# ir_remote_v3.net
KiCad netlist of a schematic drawn in EAGLE
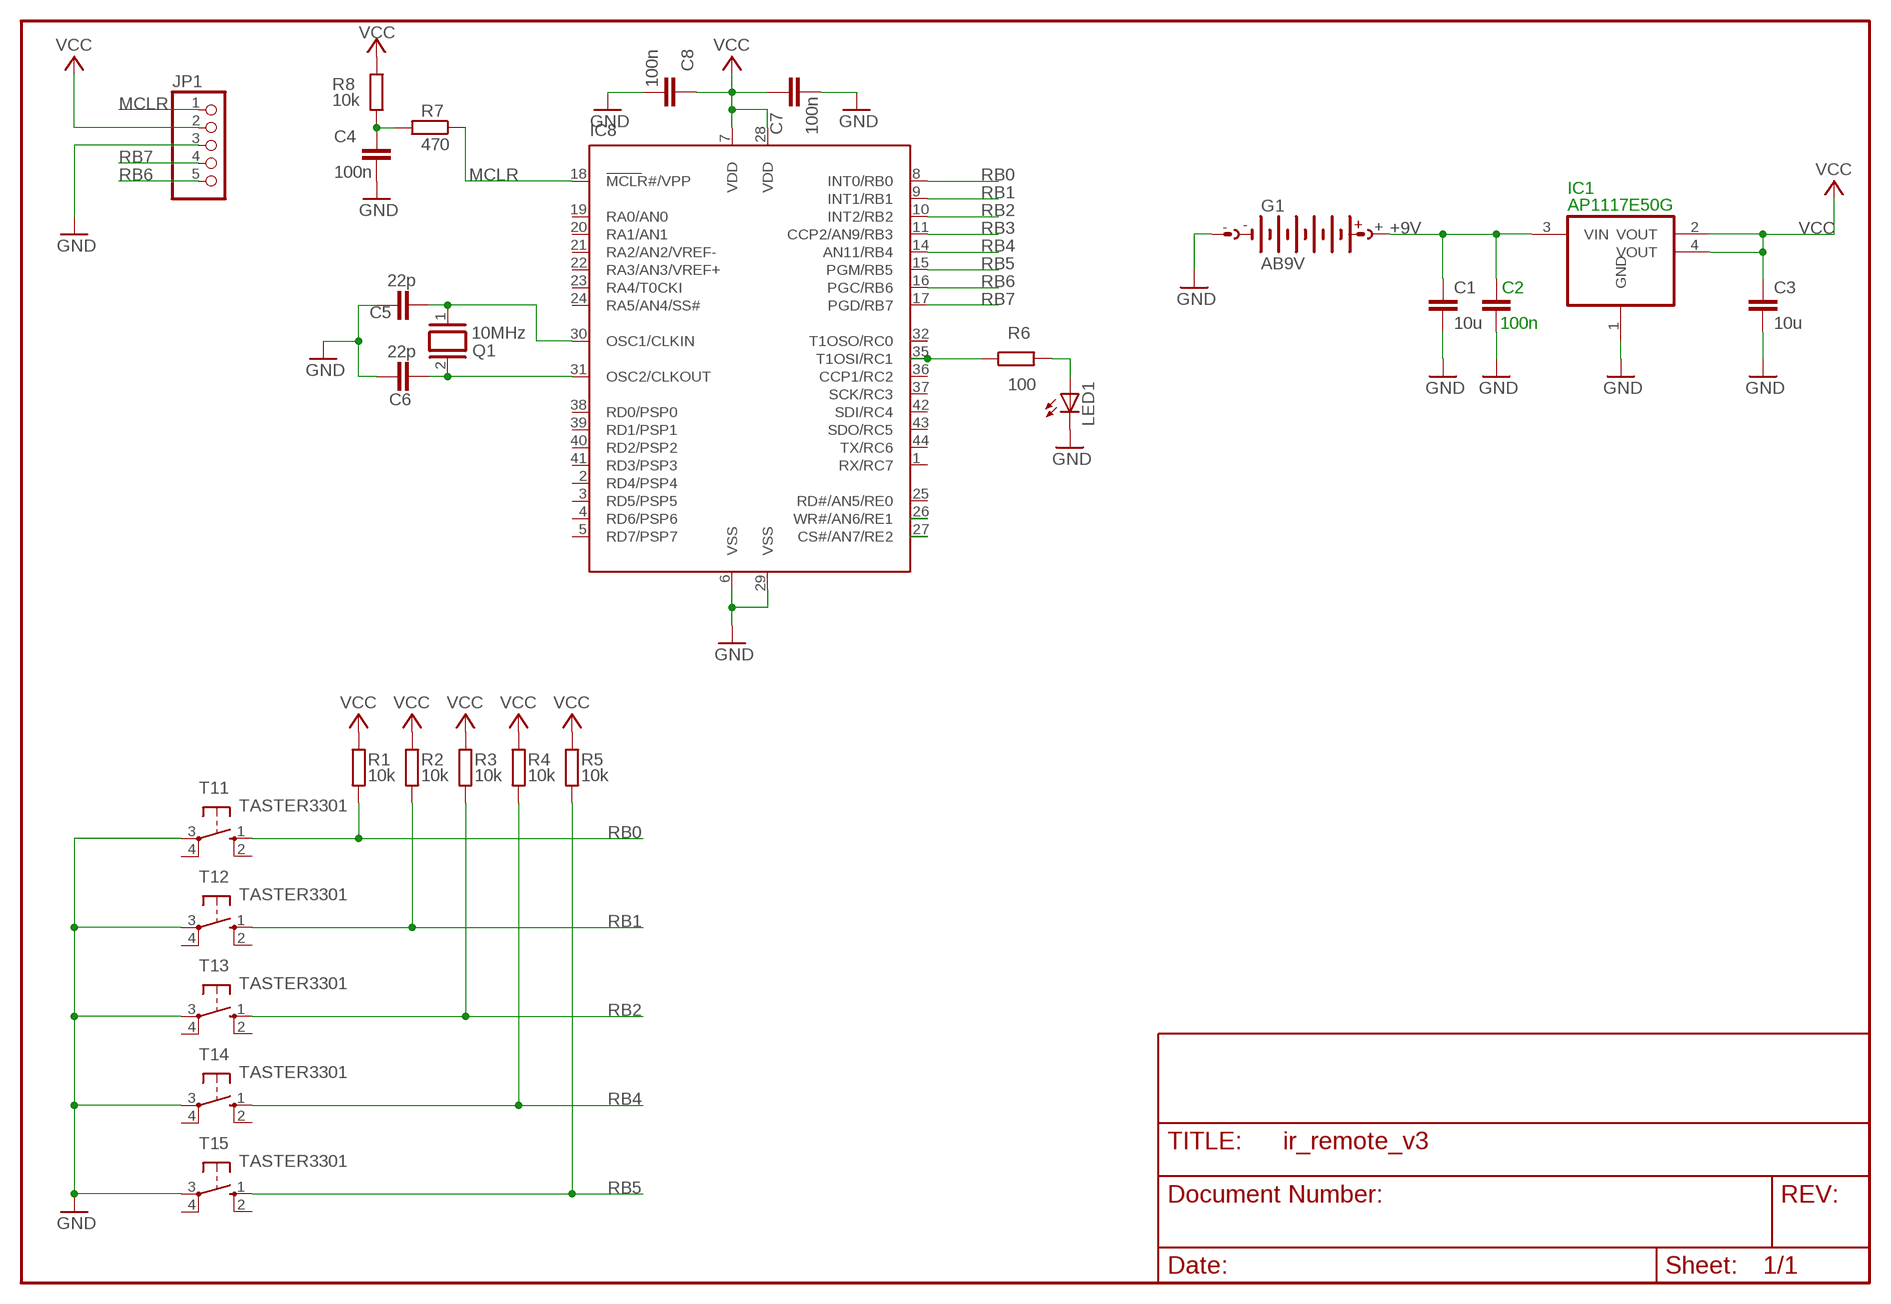
[diagram p0: schematic, sheet 1]

(export (version "E")
  (design (tool "Eeschema 10.0.6"))
  (components
    (comp (ref "C1")
      (value "10u")
      (footprint "eagle-import:C0805")
      (libsource (lib "eagle-import") (part "C-EUC0805"))
    )
    (comp (ref "C2")
      (value "100n")
      (footprint "eagle-import:C0805")
      (libsource (lib "eagle-import") (part "rcl_416_C-EUC0805"))
    )
    (comp (ref "C3")
      (value "10u")
      (footprint "eagle-import:C0805")
      (libsource (lib "eagle-import") (part "C-EUC0805"))
    )
    (comp (ref "C4")
      (value "100n")
      (footprint "eagle-import:C0805")
      (libsource (lib "eagle-import") (part "C-EUC0805"))
    )
    (comp (ref "C5")
      (value "22p")
      (footprint "eagle-import:C0603_WE")
      (libsource (lib "eagle-import") (part "C-EUC0603_WE"))
    )
    (comp (ref "C6")
      (value "22p")
      (footprint "eagle-import:C0603_WE")
      (libsource (lib "eagle-import") (part "C-EUC0603_WE"))
    )
    (comp (ref "C7")
      (value "100n")
      (footprint "eagle-import:C0805")
      (libsource (lib "eagle-import") (part "C-EUC0805"))
    )
    (comp (ref "C8")
      (value "100n")
      (footprint "eagle-import:C0805")
      (libsource (lib "eagle-import") (part "C-EUC0805"))
    )
    (comp (ref "G1")
      (value "AB9V")
      (footprint "eagle-import:AB9V")
      (libsource (lib "eagle-import") (part "AB9V"))
    )
    (comp (ref "IC1")
      (value "AP1117E50G")
      (footprint "eagle-import:SOT223")
      (libsource (lib "eagle-import") (part "REG1117-2OUT"))
    )
    (comp (ref "IC8")
      (value "PIC18F4520")
      (footprint "eagle-import:TQFP44")
      (libsource (lib "eagle-import") (part "PIC18F4520"))
    )
    (comp (ref "JP1")
      (value "PINHD-1X5")
      (footprint "eagle-import:1X05")
      (libsource (lib "eagle-import") (part "PINHD-1X5"))
    )
    (comp (ref "LED1")
      (value "LED5MM")
      (footprint "eagle-import:LED5MM")
      (libsource (lib "eagle-import") (part "LED5MM"))
    )
    (comp (ref "Q1")
      (value "10MHz")
      (footprint "eagle-import:QUARZ_HC5032_2")
      (libsource (lib "eagle-import") (part "XTAL_HC5032"))
    )
    (comp (ref "R1")
      (value "10k")
      (footprint "eagle-import:M0805")
      (libsource (lib "eagle-import") (part "R-EU_M0805"))
    )
    (comp (ref "R2")
      (value "10k")
      (footprint "eagle-import:M0805")
      (libsource (lib "eagle-import") (part "R-EU_M0805"))
    )
    (comp (ref "R3")
      (value "10k")
      (footprint "eagle-import:M0805")
      (libsource (lib "eagle-import") (part "R-EU_M0805"))
    )
    (comp (ref "R4")
      (value "10k")
      (footprint "eagle-import:M0805")
      (libsource (lib "eagle-import") (part "R-EU_M0805"))
    )
    (comp (ref "R5")
      (value "10k")
      (footprint "eagle-import:M0805")
      (libsource (lib "eagle-import") (part "R-EU_M0805"))
    )
    (comp (ref "R6")
      (value "100")
      (footprint "eagle-import:M0805")
      (libsource (lib "eagle-import") (part "R-EU_M0805"))
    )
    (comp (ref "R7")
      (value "470")
      (footprint "eagle-import:M0805")
      (libsource (lib "eagle-import") (part "R-EU_M0805"))
    )
    (comp (ref "R8")
      (value "10k")
      (footprint "eagle-import:M0805")
      (libsource (lib "eagle-import") (part "R-EU_M0805"))
    )
    (comp (ref "T11")
      (value "TASTER3301")
      (footprint "eagle-import:TASTER3301")
      (libsource (lib "eagle-import") (part "TASTER3301"))
    )
    (comp (ref "T12")
      (value "TASTER3301")
      (footprint "eagle-import:TASTER3301")
      (libsource (lib "eagle-import") (part "TASTER3301"))
    )
    (comp (ref "T13")
      (value "TASTER3301")
      (footprint "eagle-import:TASTER3301")
      (libsource (lib "eagle-import") (part "TASTER3301"))
    )
    (comp (ref "T14")
      (value "TASTER3301")
      (footprint "eagle-import:TASTER3301")
      (libsource (lib "eagle-import") (part "TASTER3301"))
    )
    (comp (ref "T15")
      (value "TASTER3301")
      (footprint "eagle-import:TASTER3301")
      (libsource (lib "eagle-import") (part "TASTER3301"))
    )
  )
  (nets
    (net (code "1") (name "/+9V") (class "Default")
      (node (ref "C1") (pin "1") (pinfunction "1_1") (pintype "passive"))
      (node (ref "C2") (pin "1") (pinfunction "1_1") (pintype "passive"))
      (node (ref "G1") (pin "+") (pinfunction "+_+") (pintype "passive"))
      (node (ref "IC1") (pin "3") (pinfunction "VIN_3") (pintype "input"))
    )
    (net (code "2") (name "/MCLR") (class "Default")
      (node (ref "IC8") (pin "18") (pinfunction "MCLR#/VPP_18") (pintype "input"))
      (node (ref "JP1") (pin "1") (pinfunction "1_1") (pintype "passive"))
      (node (ref "R7") (pin "1") (pinfunction "1_1") (pintype "passive"))
    )
    (net (code "3") (name "/RB0") (class "Default")
      (node (ref "IC8") (pin "8") (pinfunction "INT0/RB0_8") (pintype "bidirectional"))
      (node (ref "R1") (pin "2") (pinfunction "2_2") (pintype "passive"))
      (node (ref "T11") (pin "1") (pinfunction "S_1") (pintype "passive"))
    )
    (net (code "4") (name "/RB1") (class "Default")
      (node (ref "IC8") (pin "9") (pinfunction "INT1/RB1_9") (pintype "bidirectional"))
      (node (ref "R2") (pin "2") (pinfunction "2_2") (pintype "passive"))
      (node (ref "T12") (pin "1") (pinfunction "S_1") (pintype "passive"))
    )
    (net (code "5") (name "/RB2") (class "Default")
      (node (ref "IC8") (pin "10") (pinfunction "INT2/RB2_10") (pintype "bidirectional"))
      (node (ref "IC8") (pin "32") (pinfunction "T1OSO/RC0_32") (pintype "bidirectional"))
      (node (ref "R3") (pin "2") (pinfunction "2_2") (pintype "passive"))
      (node (ref "T13") (pin "1") (pinfunction "S_1") (pintype "passive"))
    )
    (net (code "6") (name "/RB3") (class "Default")
      (node (ref "IC8") (pin "11") (pinfunction "CCP2/AN9/RB3_11") (pintype "bidirectional"))
    )
    (net (code "7") (name "/RB4") (class "Default")
      (node (ref "IC8") (pin "14") (pinfunction "AN11/RB4_14") (pintype "bidirectional"))
      (node (ref "R4") (pin "2") (pinfunction "2_2") (pintype "passive"))
      (node (ref "T14") (pin "1") (pinfunction "S_1") (pintype "passive"))
    )
    (net (code "8") (name "/RB5") (class "Default")
      (node (ref "IC8") (pin "15") (pinfunction "PGM/RB5_15") (pintype "bidirectional"))
      (node (ref "R5") (pin "2") (pinfunction "2_2") (pintype "passive"))
      (node (ref "T15") (pin "1") (pinfunction "S_1") (pintype "passive"))
    )
    (net (code "9") (name "/RB6") (class "Default")
      (node (ref "IC8") (pin "16") (pinfunction "PGC/RB6_16") (pintype "bidirectional"))
      (node (ref "JP1") (pin "5") (pinfunction "5_5") (pintype "passive"))
    )
    (net (code "10") (name "/RB7") (class "Default")
      (node (ref "IC8") (pin "17") (pinfunction "PGD/RB7_17") (pintype "bidirectional"))
      (node (ref "JP1") (pin "4") (pinfunction "4_4") (pintype "passive"))
    )
    (net (code "11") (name "GND") (class "Default")
      (node (ref "C1") (pin "2") (pinfunction "2_2") (pintype "passive"))
      (node (ref "C2") (pin "2") (pinfunction "2_2") (pintype "passive"))
      (node (ref "C3") (pin "2") (pinfunction "2_2") (pintype "passive"))
      (node (ref "C4") (pin "2") (pinfunction "2_2") (pintype "passive"))
      (node (ref "C5") (pin "1") (pinfunction "1_1") (pintype "passive"))
      (node (ref "C6") (pin "1") (pinfunction "1_1") (pintype "passive"))
      (node (ref "C7") (pin "2") (pinfunction "2_2") (pintype "passive"))
      (node (ref "C8") (pin "2") (pinfunction "2_2") (pintype "passive"))
      (node (ref "G1") (pin "-") (pinfunction "-_-") (pintype "passive"))
      (node (ref "IC1") (pin "1") (pinfunction "GND_1") (pintype "power_in"))
      (node (ref "IC8") (pin "29") (pinfunction "VSS_29") (pintype "bidirectional"))
      (node (ref "IC8") (pin "6") (pinfunction "VSS_6") (pintype "bidirectional"))
      (node (ref "JP1") (pin "3") (pinfunction "3_3") (pintype "passive"))
      (node (ref "LED1") (pin "K") (pinfunction "C_K") (pintype "passive"))
      (node (ref "T11") (pin "3") (pinfunction "P_3") (pintype "passive"))
      (node (ref "T12") (pin "3") (pinfunction "P_3") (pintype "passive"))
      (node (ref "T13") (pin "3") (pinfunction "P_3") (pintype "passive"))
      (node (ref "T14") (pin "3") (pinfunction "P_3") (pintype "passive"))
      (node (ref "T15") (pin "3") (pinfunction "P_3") (pintype "passive"))
    )
    (net (code "12") (name "Net-(C4-Pad1)") (class "Default")
      (node (ref "C4") (pin "1") (pinfunction "1_1") (pintype "passive"))
      (node (ref "R7") (pin "2") (pinfunction "2_2") (pintype "passive"))
      (node (ref "R8") (pin "2") (pinfunction "2_2") (pintype "passive"))
    )
    (net (code "13") (name "Net-(IC8-OSC1{slash}CLKIN)") (class "Default")
      (node (ref "C5") (pin "2") (pinfunction "2_2") (pintype "passive"))
      (node (ref "IC8") (pin "30") (pinfunction "OSC1/CLKIN_30") (pintype "input"))
      (node (ref "Q1") (pin "1") (pinfunction "1_1") (pintype "passive"))
    )
    (net (code "14") (name "Net-(IC8-OSC2{slash}CLKOUT)") (class "Default")
      (node (ref "C6") (pin "2") (pinfunction "2_2") (pintype "passive"))
      (node (ref "IC8") (pin "31") (pinfunction "OSC2/CLKOUT_31") (pintype "output"))
      (node (ref "Q1") (pin "2") (pinfunction "2_2") (pintype "passive"))
    )
    (net (code "15") (name "Net-(IC8-T1OSI{slash}RC1)") (class "Default")
      (node (ref "IC8") (pin "35") (pinfunction "T1OSI/RC1_35") (pintype "bidirectional"))
      (node (ref "R6") (pin "1") (pinfunction "1_1") (pintype "passive"))
    )
    (net (code "16") (name "Net-(LED1-PadA)") (class "Default")
      (node (ref "LED1") (pin "A") (pinfunction "A_A") (pintype "passive"))
      (node (ref "R6") (pin "2") (pinfunction "2_2") (pintype "passive"))
    )
    (net (code "17") (name "VCC") (class "Default")
      (node (ref "C3") (pin "1") (pinfunction "1_1") (pintype "passive"))
      (node (ref "C7") (pin "1") (pinfunction "1_1") (pintype "passive"))
      (node (ref "C8") (pin "1") (pinfunction "1_1") (pintype "passive"))
      (node (ref "IC1") (pin "2") (pinfunction "VOUT_2") (pintype "output"))
      (node (ref "IC1") (pin "4") (pinfunction "VOUT_4") (pintype "bidirectional"))
      (node (ref "IC8") (pin "28") (pinfunction "VDD_28") (pintype "bidirectional"))
      (node (ref "IC8") (pin "7") (pinfunction "VDD_7") (pintype "bidirectional"))
      (node (ref "JP1") (pin "2") (pinfunction "2_2") (pintype "passive"))
      (node (ref "R1") (pin "1") (pinfunction "1_1") (pintype "passive"))
      (node (ref "R2") (pin "1") (pinfunction "1_1") (pintype "passive"))
      (node (ref "R3") (pin "1") (pinfunction "1_1") (pintype "passive"))
      (node (ref "R4") (pin "1") (pinfunction "1_1") (pintype "passive"))
      (node (ref "R5") (pin "1") (pinfunction "1_1") (pintype "passive"))
      (node (ref "R8") (pin "1") (pinfunction "1_1") (pintype "passive"))
    )
    (net (code "18") (name "unconnected-(IC8-CCP1{slash}RC2-Pad36)") (class "Default")
      (node (ref "IC8") (pin "36") (pinfunction "CCP1/RC2_36") (pintype "bidirectional"))
    )
    (net (code "19") (name "unconnected-(IC8-CS#{slash}AN7{slash}RE2-Pad27)") (class "Default")
      (node (ref "IC8") (pin "27") (pinfunction "CS#/AN7/RE2_27") (pintype "bidirectional"))
    )
    (net (code "20") (name "unconnected-(IC8-RA0{slash}AN0-Pad19)") (class "Default")
      (node (ref "IC8") (pin "19") (pinfunction "RA0/AN0_19") (pintype "bidirectional"))
    )
    (net (code "21") (name "unconnected-(IC8-RA1{slash}AN1-Pad20)") (class "Default")
      (node (ref "IC8") (pin "20") (pinfunction "RA1/AN1_20") (pintype "bidirectional"))
    )
    (net (code "22") (name "unconnected-(IC8-RA2{slash}AN2{slash}VREF--Pad21)") (class "Default")
      (node (ref "IC8") (pin "21") (pinfunction "RA2/AN2/VREF-_21") (pintype "bidirectional"))
    )
    (net (code "23") (name "unconnected-(IC8-RA3{slash}AN3{slash}VREF+-Pad22)") (class "Default")
      (node (ref "IC8") (pin "22") (pinfunction "RA3/AN3/VREF+_22") (pintype "bidirectional"))
    )
    (net (code "24") (name "unconnected-(IC8-RA4{slash}T0CKI-Pad23)") (class "Default")
      (node (ref "IC8") (pin "23") (pinfunction "RA4/T0CKI_23") (pintype "bidirectional"))
    )
    (net (code "25") (name "unconnected-(IC8-RA5{slash}AN4{slash}SS#-Pad24)") (class "Default")
      (node (ref "IC8") (pin "24") (pinfunction "RA5/AN4/SS#_24") (pintype "bidirectional"))
    )
    (net (code "26") (name "unconnected-(IC8-RD#{slash}AN5{slash}RE0-Pad25)") (class "Default")
      (node (ref "IC8") (pin "25") (pinfunction "RD#/AN5/RE0_25") (pintype "bidirectional"))
    )
    (net (code "27") (name "unconnected-(IC8-RD0{slash}PSP0-Pad38)") (class "Default")
      (node (ref "IC8") (pin "38") (pinfunction "RD0/PSP0_38") (pintype "bidirectional"))
    )
    (net (code "28") (name "unconnected-(IC8-RD1{slash}PSP1-Pad39)") (class "Default")
      (node (ref "IC8") (pin "39") (pinfunction "RD1/PSP1_39") (pintype "bidirectional"))
    )
    (net (code "29") (name "unconnected-(IC8-RD2{slash}PSP2-Pad40)") (class "Default")
      (node (ref "IC8") (pin "40") (pinfunction "RD2/PSP2_40") (pintype "bidirectional"))
    )
    (net (code "30") (name "unconnected-(IC8-RD3{slash}PSP3-Pad41)") (class "Default")
      (node (ref "IC8") (pin "41") (pinfunction "RD3/PSP3_41") (pintype "bidirectional"))
    )
    (net (code "31") (name "unconnected-(IC8-RD4{slash}PSP4-Pad2)") (class "Default")
      (node (ref "IC8") (pin "2") (pinfunction "RD4/PSP4_2") (pintype "bidirectional"))
    )
    (net (code "32") (name "unconnected-(IC8-RD5{slash}PSP5-Pad3)") (class "Default")
      (node (ref "IC8") (pin "3") (pinfunction "RD5/PSP5_3") (pintype "bidirectional"))
    )
    (net (code "33") (name "unconnected-(IC8-RD6{slash}PSP6-Pad4)") (class "Default")
      (node (ref "IC8") (pin "4") (pinfunction "RD6/PSP6_4") (pintype "bidirectional"))
    )
    (net (code "34") (name "unconnected-(IC8-RD7{slash}PSP7-Pad5)") (class "Default")
      (node (ref "IC8") (pin "5") (pinfunction "RD7/PSP7_5") (pintype "bidirectional"))
    )
    (net (code "35") (name "unconnected-(IC8-RX{slash}RC7-Pad1)") (class "Default")
      (node (ref "IC8") (pin "1") (pinfunction "RX/RC7_1") (pintype "bidirectional"))
    )
    (net (code "36") (name "unconnected-(IC8-SCK{slash}RC3-Pad37)") (class "Default")
      (node (ref "IC8") (pin "37") (pinfunction "SCK/RC3_37") (pintype "bidirectional"))
    )
    (net (code "37") (name "unconnected-(IC8-SDI{slash}RC4-Pad42)") (class "Default")
      (node (ref "IC8") (pin "42") (pinfunction "SDI/RC4_42") (pintype "bidirectional"))
    )
    (net (code "38") (name "unconnected-(IC8-SDO{slash}RC5-Pad43)") (class "Default")
      (node (ref "IC8") (pin "43") (pinfunction "SDO/RC5_43") (pintype "bidirectional"))
    )
    (net (code "39") (name "unconnected-(IC8-TX{slash}RC6-Pad44)") (class "Default")
      (node (ref "IC8") (pin "44") (pinfunction "TX/RC6_44") (pintype "bidirectional"))
    )
    (net (code "40") (name "unconnected-(IC8-WR#{slash}AN6{slash}RE1-Pad26)") (class "Default")
      (node (ref "IC8") (pin "26") (pinfunction "WR#/AN6/RE1_26") (pintype "bidirectional"))
    )
    (net (code "41") (name "unconnected-(T11-P1-Pad4)") (class "Default")
      (node (ref "T11") (pin "4") (pinfunction "P1_4") (pintype "passive"))
    )
    (net (code "42") (name "unconnected-(T11-S1-Pad2)") (class "Default")
      (node (ref "T11") (pin "2") (pinfunction "S1_2") (pintype "passive"))
    )
    (net (code "43") (name "unconnected-(T12-P1-Pad4)") (class "Default")
      (node (ref "T12") (pin "4") (pinfunction "P1_4") (pintype "passive"))
    )
    (net (code "44") (name "unconnected-(T12-S1-Pad2)") (class "Default")
      (node (ref "T12") (pin "2") (pinfunction "S1_2") (pintype "passive"))
    )
    (net (code "45") (name "unconnected-(T13-P1-Pad4)") (class "Default")
      (node (ref "T13") (pin "4") (pinfunction "P1_4") (pintype "passive"))
    )
    (net (code "46") (name "unconnected-(T13-S1-Pad2)") (class "Default")
      (node (ref "T13") (pin "2") (pinfunction "S1_2") (pintype "passive"))
    )
    (net (code "47") (name "unconnected-(T14-P1-Pad4)") (class "Default")
      (node (ref "T14") (pin "4") (pinfunction "P1_4") (pintype "passive"))
    )
    (net (code "48") (name "unconnected-(T14-S1-Pad2)") (class "Default")
      (node (ref "T14") (pin "2") (pinfunction "S1_2") (pintype "passive"))
    )
    (net (code "49") (name "unconnected-(T15-P1-Pad4)") (class "Default")
      (node (ref "T15") (pin "4") (pinfunction "P1_4") (pintype "passive"))
    )
    (net (code "50") (name "unconnected-(T15-S1-Pad2)") (class "Default")
      (node (ref "T15") (pin "2") (pinfunction "S1_2") (pintype "passive"))
    )
  )
)
